# reed_switch.net
KiCad netlist of a schematic drawn in Altium Designer
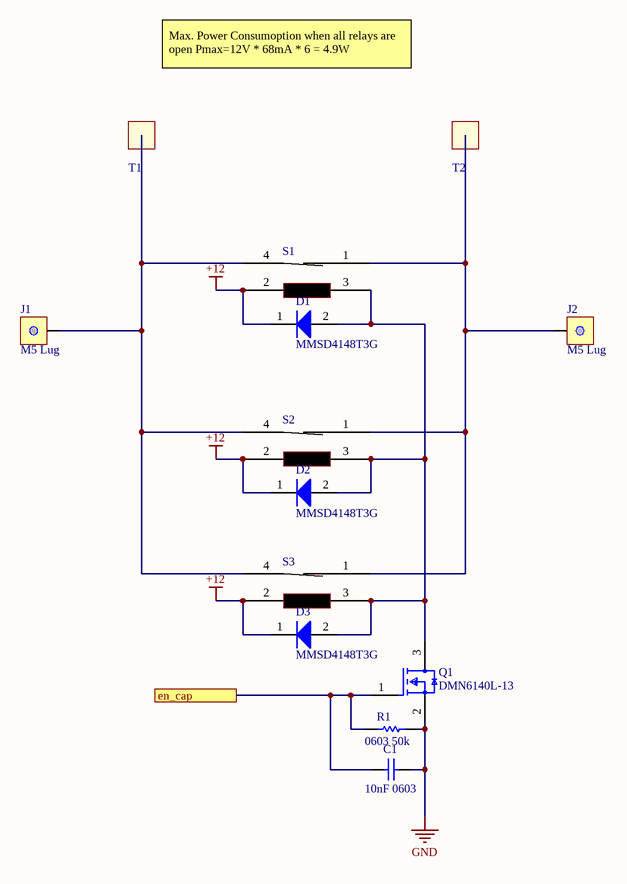
[diagram p0: reed_switch.SchDoc]

(export (version "E")
  (design (tool "Eeschema 10.0.6"))
  (components
    (comp (ref "C1")
      (value "10nF 0603")
      (footprint "CAP 0603_1608")
      (description "Capacitor")
      (fields (field (name "PUBLISHER") "Altium Limited"))
      (libsource (lib "Miscellaneous Devices") (part "Cap"))
    )
    (comp (ref "D1")
      (value "MMSD4148T3G")
      (footprint "ONSC-SOD-123-2-425-04_V")
      (description "Switching Diode, 2-Pin SOD-123, Pb-Free, Tape and Reel")
      (fields (field (name "MANUFACTURER") "On Semiconductor"))
      (libsource (lib "Altium Content Vault") (part "ONSC-D-K1A2-2"))
    )
    (comp (ref "D2")
      (value "MMSD4148T3G")
      (footprint "ONSC-SOD-123-2-425-04_V")
      (description "Switching Diode, 2-Pin SOD-123, Pb-Free, Tape and Reel")
      (fields (field (name "MANUFACTURER") "On Semiconductor"))
      (libsource (lib "Altium Content Vault") (part "ONSC-D-K1A2-2"))
    )
    (comp (ref "D3")
      (value "MMSD4148T3G")
      (footprint "ONSC-SOD-123-2-425-04_V")
      (description "Switching Diode, 2-Pin SOD-123, Pb-Free, Tape and Reel")
      (fields (field (name "MANUFACTURER") "On Semiconductor"))
      (libsource (lib "Altium Content Vault") (part "ONSC-D-K1A2-2"))
    )
    (comp (ref "J1")
      (value "M5 Lug")
      (footprint "lug_pad_10mm_m5")
      (libsource (lib "coil_driver_lib") (part "lug_pad_10mm_m5"))
    )
    (comp (ref "J2")
      (value "M5 Lug")
      (footprint "lug_pad_10mm_m5")
      (libsource (lib "") (part "lug_pad_10mm_m5_1"))
    )
    (comp (ref "Q1")
      (value "DMN6140L-13")
      (footprint "FP-SOT23-MFG")
      (description "MOSFET N-CH 60V 1.6A SOT23")
      (fields
        (field (name "OCTOPART") "https://octopart.com/dmn6140l-13-diodes+inc.-38898616")
        (field (name "MANUFACTURER") "Diodes Inc.")
      )
      (libsource (lib "Altium Content Vault") (part "0a9ea7c96deaaede766a5b531c28de0"))
    )
    (comp (ref "R1")
      (value "0603 50k")
      (footprint "RES 0603_1608")
      (description "Resistor")
      (fields (field (name "PUBLISHER") "Altium Limited"))
      (libsource (lib "Miscellaneous Devices") (part "Res1"))
    )
    (comp (ref "S1")
      (value "Reed Relay 5A 3500kV / 7500kV (AC & DC)")
      (footprint "reed_relay_comus_3350-4275-126")
      (description "3500kV (AC & DC) breaking capacity @ 200W\r\n7500kV (AC & DC) minimum dielectric strength")
      (libsource (lib "coil_driver_lib") (part "reed_relay_3350-4275-126"))
    )
    (comp (ref "S2")
      (value "Reed Relay 5A 3500kV / 7500kV (AC & DC)")
      (footprint "reed_relay_comus_3350-4275-126")
      (description "3500kV (AC & DC) breaking capacity @ 200W\r\n7500kV (AC & DC) minimum dielectric strength")
      (libsource (lib "coil_driver_lib") (part "reed_relay_3350-4275-126"))
    )
    (comp (ref "S3")
      (value "Reed Relay 5A 3500kV / 7500kV (AC & DC)")
      (footprint "reed_relay_comus_3350-4275-126")
      (description "3500kV (AC & DC) breaking capacity @ 200W\r\n7500kV (AC & DC) minimum dielectric strength")
      (libsource (lib "coil_driver_lib") (part "reed_relay_3350-4275-126"))
    )
    (comp (ref "T1")
      (value "pwr_connector_quick")
      (footprint "pcb_quick_power_connector")
      (libsource (lib "coil_driver_lib") (part "pwr_connector_quick"))
    )
    (comp (ref "T2")
      (value "pwr_connector_quick")
      (footprint "pcb_quick_power_connector")
      (libsource (lib "coil_driver_lib") (part "pwr_connector_quick"))
    )
  )
  (nets
    (net (code "1") (name "+12") (class "Default")
      (node (ref "D1") (pin "1") (pinfunction "K_1") (pintype "passive"))
      (node (ref "D2") (pin "1") (pinfunction "K_1") (pintype "passive"))
      (node (ref "D3") (pin "1") (pinfunction "K_1") (pintype "passive"))
      (node (ref "S1") (pin "2") (pintype "passive"))
      (node (ref "S2") (pin "2") (pintype "passive"))
      (node (ref "S3") (pin "2") (pintype "passive"))
    )
    (net (code "2") (name "/en_cap") (class "Default")
      (node (ref "C1") (pin "1") (pinfunction "1_1") (pintype "passive"))
      (node (ref "Q1") (pin "1") (pinfunction "G_1") (pintype "passive"))
      (node (ref "R1") (pin "1") (pinfunction "1_1") (pintype "passive"))
    )
    (net (code "3") (name "GND") (class "Default")
      (node (ref "C1") (pin "2") (pinfunction "2_2") (pintype "passive"))
      (node (ref "Q1") (pin "2") (pinfunction "S_2") (pintype "passive"))
      (node (ref "R1") (pin "2") (pinfunction "2_2") (pintype "passive"))
    )
    (net (code "4") (name "Net-(D1-A)") (class "Default")
      (node (ref "D1") (pin "2") (pinfunction "A_2") (pintype "passive"))
      (node (ref "D2") (pin "2") (pinfunction "A_2") (pintype "passive"))
      (node (ref "D3") (pin "2") (pinfunction "A_2") (pintype "passive"))
      (node (ref "Q1") (pin "3") (pinfunction "D_3") (pintype "passive"))
      (node (ref "S1") (pin "3") (pintype "passive"))
      (node (ref "S2") (pin "3") (pintype "passive"))
      (node (ref "S3") (pin "3") (pintype "passive"))
    )
    (net (code "5") (name "Net-(J1-Pad1)") (class "Default")
      (node (ref "J1") (pin "1") (pinfunction "1_1") (pintype "passive"))
      (node (ref "S1") (pin "4") (pintype "passive"))
      (node (ref "S2") (pin "4") (pintype "passive"))
      (node (ref "S3") (pin "4") (pintype "passive"))
      (node (ref "T1") (pin "1") (pinfunction "1_1") (pintype "passive"))
    )
    (net (code "6") (name "Net-(J2-Pad1)") (class "Default")
      (node (ref "J2") (pin "1") (pinfunction "1_1") (pintype "passive"))
      (node (ref "S1") (pin "1") (pintype "passive"))
      (node (ref "S2") (pin "1") (pintype "passive"))
      (node (ref "S3") (pin "1") (pintype "passive"))
      (node (ref "T2") (pin "1") (pinfunction "1_1") (pintype "passive"))
    )
  )
)
